# Power_LDO_15V.net
KiCad netlist of a schematic drawn in Altium Designer
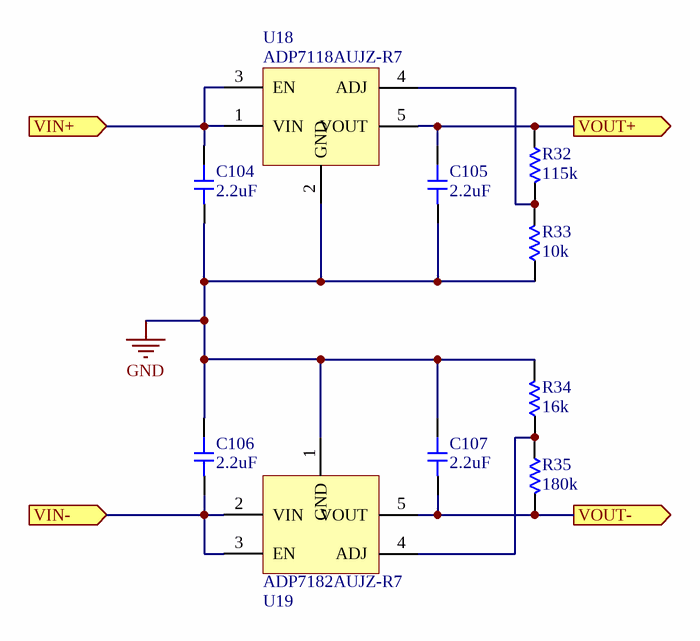
[diagram p0: Power_LDO_15V.SchDoc]

(export (version "E")
  (design (tool "Eeschema 10.0.6"))
  (components
    (comp (ref "C104")
      (value "2.2uF")
      (footprint "0603-CAP")
      (description "Capacitor")
      (libsource (lib "AMDC") (part "Capacitor"))
    )
    (comp (ref "C105")
      (value "2.2uF")
      (footprint "0603-CAP")
      (description "Capacitor")
      (libsource (lib "AMDC") (part "Capacitor"))
    )
    (comp (ref "C106")
      (value "2.2uF")
      (footprint "0603-CAP")
      (description "Capacitor")
      (libsource (lib "AMDC") (part "Capacitor"))
    )
    (comp (ref "C107")
      (value "2.2uF")
      (footprint "0603-CAP")
      (description "Capacitor")
      (libsource (lib "AMDC") (part "Capacitor"))
    )
    (comp (ref "R32")
      (value "115k")
      (footprint "0603-RES")
      (description "Resistor")
      (libsource (lib "AMDC") (part "Resistor"))
    )
    (comp (ref "R33")
      (value "10k")
      (footprint "0603-RES")
      (description "Resistor")
      (libsource (lib "AMDC") (part "Resistor"))
    )
    (comp (ref "R34")
      (value "16k")
      (footprint "0603-RES")
      (description "Resistor")
      (libsource (lib "AMDC") (part "Resistor"))
    )
    (comp (ref "R35")
      (value "180k")
      (footprint "0603-RES")
      (description "Resistor")
      (libsource (lib "AMDC") (part "Resistor"))
    )
    (comp (ref "U18")
      (value "ADP7118AUJZ-R7")
      (footprint "TSOT-23")
      (description "IC REG LINEAR 200MA TSOT23-5")
      (libsource (lib "AMDC") (part "ADP7118AUJZ-R7"))
    )
    (comp (ref "U19")
      (value "ADP7182AUJZ-R7")
      (footprint "TSOT-23")
      (description "IC REG LINEAR 200MA 5TSOT")
      (libsource (lib "AMDC") (part "ADP7182AUJZ-R7"))
    )
  )
  (nets
    (net (code "1") (name "/VIN+") (class "Default")
      (node (ref "C104") (pin "2") (pinfunction "2_2") (pintype "passive"))
      (node (ref "U18") (pin "1") (pinfunction "VIN_1") (pintype "passive"))
      (node (ref "U18") (pin "3") (pinfunction "EN_3") (pintype "passive"))
    )
    (net (code "2") (name "/VIN-") (class "Default")
      (node (ref "C106") (pin "1") (pinfunction "1_1") (pintype "passive"))
      (node (ref "U19") (pin "2") (pinfunction "VIN_2") (pintype "passive"))
      (node (ref "U19") (pin "3") (pinfunction "EN_3") (pintype "passive"))
    )
    (net (code "3") (name "/VOUT+") (class "Default")
      (node (ref "C105") (pin "2") (pinfunction "2_2") (pintype "passive"))
      (node (ref "R32") (pin "1") (pinfunction "1_1") (pintype "passive"))
      (node (ref "U18") (pin "5") (pinfunction "VOUT_5") (pintype "passive"))
    )
    (net (code "4") (name "/VOUT-") (class "Default")
      (node (ref "C107") (pin "1") (pinfunction "1_1") (pintype "passive"))
      (node (ref "R35") (pin "2") (pinfunction "2_2") (pintype "passive"))
      (node (ref "U19") (pin "5") (pinfunction "VOUT_5") (pintype "passive"))
    )
    (net (code "5") (name "GND") (class "Default")
      (node (ref "C104") (pin "1") (pinfunction "1_1") (pintype "passive"))
      (node (ref "C105") (pin "1") (pinfunction "1_1") (pintype "passive"))
      (node (ref "C106") (pin "2") (pinfunction "2_2") (pintype "passive"))
      (node (ref "C107") (pin "2") (pinfunction "2_2") (pintype "passive"))
      (node (ref "R33") (pin "1") (pinfunction "1_1") (pintype "passive"))
      (node (ref "R34") (pin "2") (pinfunction "2_2") (pintype "passive"))
      (node (ref "U18") (pin "2") (pinfunction "GND_2") (pintype "passive"))
      (node (ref "U19") (pin "1") (pinfunction "GND_1") (pintype "passive"))
    )
    (net (code "6") (name "Net-(U18-ADJ)") (class "Default")
      (node (ref "R32") (pin "2") (pinfunction "2_2") (pintype "passive"))
      (node (ref "R33") (pin "2") (pinfunction "2_2") (pintype "passive"))
      (node (ref "U18") (pin "4") (pinfunction "ADJ_4") (pintype "passive"))
    )
    (net (code "7") (name "Net-(U19-ADJ)") (class "Default")
      (node (ref "R34") (pin "1") (pinfunction "1_1") (pintype "passive"))
      (node (ref "R35") (pin "1") (pinfunction "1_1") (pintype "passive"))
      (node (ref "U19") (pin "4") (pinfunction "ADJ_4") (pintype "passive"))
    )
  )
)
